# cp300_frehd.net
KiCad netlist of a schematic drawn in EAGLE
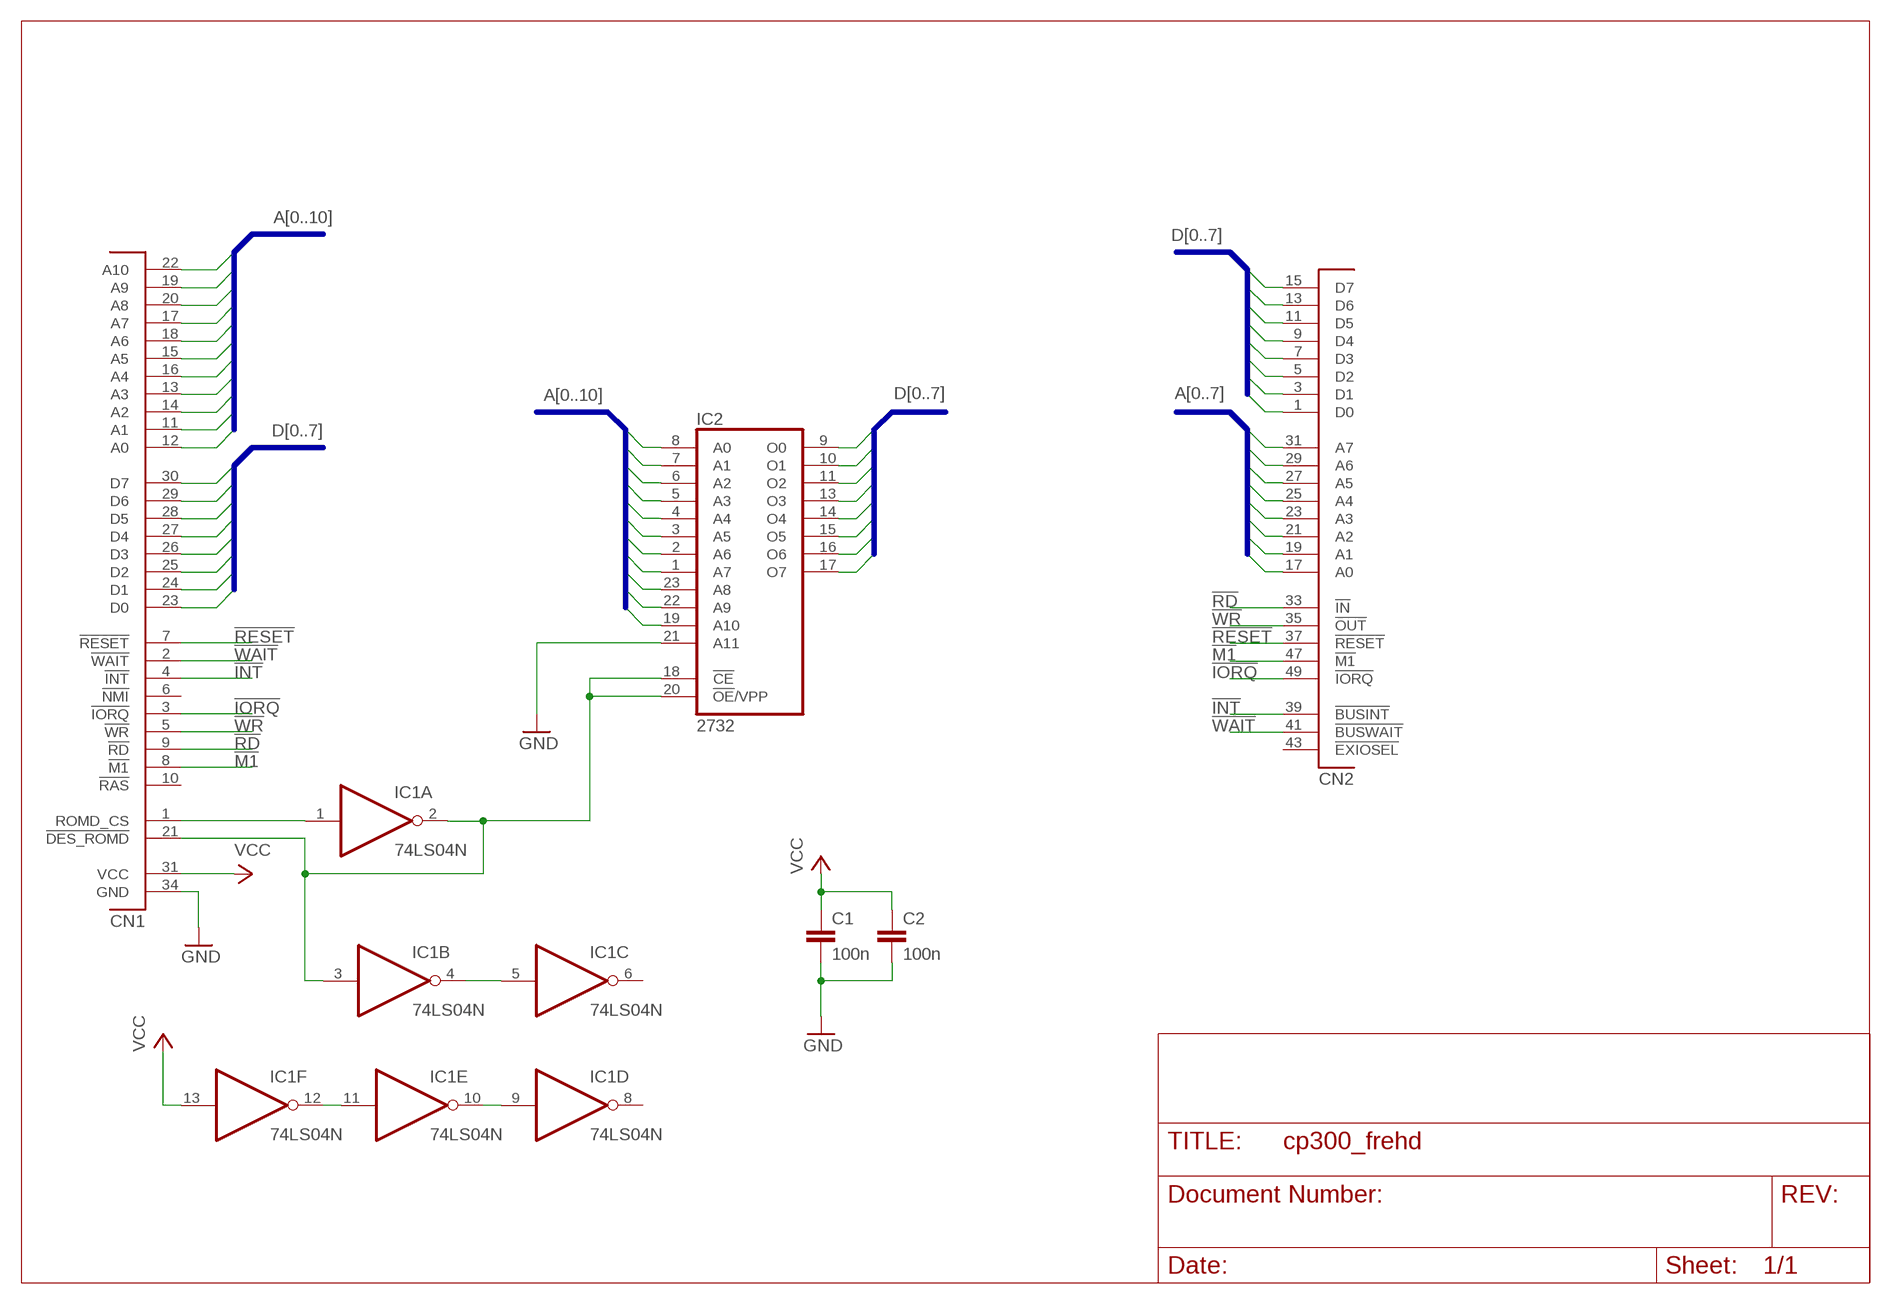
[diagram p0: schematic, sheet 1]

(export (version "E")
  (design (tool "Eeschema 10.0.6"))
  (components
    (comp (ref "C1")
      (value "100n")
      (footprint "eagle-import:C050-024X044")
      (libsource (lib "eagle-import") (part "C-EU050-024X044"))
    )
    (comp (ref "C2")
      (value "100n")
      (footprint "eagle-import:C050-024X044")
      (libsource (lib "eagle-import") (part "C-EU050-024X044"))
    )
    (comp (ref "CN1")
      (value "CP300_EXPA")
      (footprint "eagle-import:2X17")
      (libsource (lib "eagle-import") (part "CP300_EXPA"))
    )
    (comp (ref "CN2")
      (value "TRS80_EXPA")
      (footprint "eagle-import:2X25")
      (libsource (lib "eagle-import") (part "TRS80_EXPA"))
    )
    (comp (ref "IC1")
      (value "74LS04N")
      (footprint "eagle-import:DIL14")
      (libsource (lib "eagle-import") (part "7404NLS"))
    )
    (comp (ref "IC2")
      (value "2732")
      (footprint "eagle-import:DIL24")
      (libsource (lib "eagle-import") (part "2732"))
    )
  )
  (nets
    (net (code "1") (name "/A0") (class "Default")
      (node (ref "CN1") (pin "12") (pinfunction "A0_12") (pintype "output"))
      (node (ref "CN2") (pin "17") (pinfunction "A0_17") (pintype "output"))
      (node (ref "IC2") (pin "8") (pinfunction "A0_8") (pintype "input"))
    )
    (net (code "2") (name "/A1") (class "Default")
      (node (ref "CN1") (pin "11") (pinfunction "A1_11") (pintype "output"))
      (node (ref "CN2") (pin "19") (pinfunction "A1_19") (pintype "output"))
      (node (ref "IC2") (pin "7") (pinfunction "A1_7") (pintype "input"))
    )
    (net (code "3") (name "/A2") (class "Default")
      (node (ref "CN1") (pin "14") (pinfunction "A2_14") (pintype "output"))
      (node (ref "CN2") (pin "21") (pinfunction "A2_21") (pintype "output"))
      (node (ref "IC2") (pin "6") (pinfunction "A2_6") (pintype "input"))
    )
    (net (code "4") (name "/A3") (class "Default")
      (node (ref "CN1") (pin "13") (pinfunction "A3_13") (pintype "output"))
      (node (ref "CN2") (pin "23") (pinfunction "A3_23") (pintype "output"))
      (node (ref "IC2") (pin "5") (pinfunction "A3_5") (pintype "input"))
    )
    (net (code "5") (name "/A4") (class "Default")
      (node (ref "CN1") (pin "16") (pinfunction "A4_16") (pintype "output"))
      (node (ref "CN2") (pin "25") (pinfunction "A4_25") (pintype "output"))
      (node (ref "IC2") (pin "4") (pinfunction "A4_4") (pintype "input"))
    )
    (net (code "6") (name "/A5") (class "Default")
      (node (ref "CN1") (pin "15") (pinfunction "A5_15") (pintype "output"))
      (node (ref "CN2") (pin "27") (pinfunction "A5_27") (pintype "output"))
      (node (ref "CN2") (pin "29") (pinfunction "A6_29") (pintype "output"))
      (node (ref "IC2") (pin "3") (pinfunction "A5_3") (pintype "input"))
    )
    (net (code "7") (name "/A6") (class "Default")
      (node (ref "CN1") (pin "18") (pinfunction "A6_18") (pintype "output"))
      (node (ref "IC2") (pin "2") (pinfunction "A6_2") (pintype "input"))
    )
    (net (code "8") (name "/A7") (class "Default")
      (node (ref "CN1") (pin "17") (pinfunction "A7_17") (pintype "output"))
      (node (ref "CN2") (pin "31") (pinfunction "A7_31") (pintype "output"))
      (node (ref "IC2") (pin "1") (pinfunction "A7_1") (pintype "input"))
    )
    (net (code "9") (name "/A8") (class "Default")
      (node (ref "CN1") (pin "20") (pinfunction "A8_20") (pintype "output"))
      (node (ref "IC2") (pin "23") (pinfunction "A8_23") (pintype "input"))
    )
    (net (code "10") (name "/A9") (class "Default")
      (node (ref "CN1") (pin "19") (pinfunction "A9_19") (pintype "output"))
      (node (ref "IC2") (pin "22") (pinfunction "A9_22") (pintype "input"))
    )
    (net (code "11") (name "/A10") (class "Default")
      (node (ref "CN1") (pin "22") (pinfunction "A10_22") (pintype "output"))
      (node (ref "IC2") (pin "19") (pinfunction "A10_19") (pintype "input"))
    )
    (net (code "14") (name "/D0") (class "Default")
      (node (ref "CN1") (pin "23") (pinfunction "D0_23") (pintype "bidirectional"))
      (node (ref "CN2") (pin "1") (pinfunction "D0_1") (pintype "bidirectional"))
      (node (ref "IC2") (pin "9") (pinfunction "O0_9") (pintype "tri_state"))
    )
    (net (code "15") (name "/D1") (class "Default")
      (node (ref "CN1") (pin "24") (pinfunction "D1_24") (pintype "bidirectional"))
      (node (ref "CN2") (pin "3") (pinfunction "D1_3") (pintype "bidirectional"))
      (node (ref "IC2") (pin "10") (pinfunction "O1_10") (pintype "tri_state"))
    )
    (net (code "16") (name "/D2") (class "Default")
      (node (ref "CN1") (pin "25") (pinfunction "D2_25") (pintype "bidirectional"))
      (node (ref "CN2") (pin "5") (pinfunction "D2_5") (pintype "bidirectional"))
      (node (ref "IC2") (pin "11") (pinfunction "O2_11") (pintype "tri_state"))
    )
    (net (code "17") (name "/D3") (class "Default")
      (node (ref "CN1") (pin "26") (pinfunction "D3_26") (pintype "bidirectional"))
      (node (ref "CN2") (pin "7") (pinfunction "D3_7") (pintype "bidirectional"))
      (node (ref "IC2") (pin "13") (pinfunction "O3_13") (pintype "tri_state"))
    )
    (net (code "18") (name "/D4") (class "Default")
      (node (ref "CN1") (pin "27") (pinfunction "D4_27") (pintype "bidirectional"))
      (node (ref "CN2") (pin "9") (pinfunction "D4_9") (pintype "bidirectional"))
      (node (ref "IC2") (pin "14") (pinfunction "O4_14") (pintype "tri_state"))
    )
    (net (code "19") (name "/D5") (class "Default")
      (node (ref "CN1") (pin "28") (pinfunction "D5_28") (pintype "bidirectional"))
      (node (ref "CN2") (pin "11") (pinfunction "D5_11") (pintype "bidirectional"))
      (node (ref "IC2") (pin "15") (pinfunction "O5_15") (pintype "tri_state"))
    )
    (net (code "20") (name "/D6") (class "Default")
      (node (ref "CN1") (pin "29") (pinfunction "D6_29") (pintype "bidirectional"))
      (node (ref "CN2") (pin "13") (pinfunction "D6_13") (pintype "bidirectional"))
      (node (ref "IC2") (pin "16") (pinfunction "O6_16") (pintype "tri_state"))
    )
    (net (code "21") (name "/D7") (class "Default")
      (node (ref "CN1") (pin "30") (pinfunction "D7_30") (pintype "bidirectional"))
      (node (ref "CN2") (pin "15") (pinfunction "D7_15") (pintype "bidirectional"))
      (node (ref "IC2") (pin "17") (pinfunction "O7_17") (pintype "tri_state"))
    )
    (net (code "23") (name "/~{INT}") (class "Default")
      (node (ref "CN1") (pin "4") (pinfunction "~{INT}_4") (pintype "input"))
      (node (ref "CN2") (pin "39") (pinfunction "~{BUSINT}_39") (pintype "input"))
    )
    (net (code "24") (name "/~{IORQ}") (class "Default")
      (node (ref "CN1") (pin "3") (pinfunction "~{IORQ}_3") (pintype "output"))
      (node (ref "CN2") (pin "49") (pinfunction "~{IORQ}_49") (pintype "output"))
    )
    (net (code "25") (name "/~{M1}") (class "Default")
      (node (ref "CN1") (pin "8") (pinfunction "~{M1}_8") (pintype "output"))
      (node (ref "CN2") (pin "47") (pinfunction "~{M1}_47") (pintype "output"))
    )
    (net (code "26") (name "/~{RD}") (class "Default")
      (node (ref "CN1") (pin "9") (pinfunction "~{RD}_9") (pintype "output"))
      (node (ref "CN2") (pin "33") (pinfunction "~{IN}_33") (pintype "output"))
    )
    (net (code "27") (name "/~{RESET}") (class "Default")
      (node (ref "CN1") (pin "7") (pinfunction "~{RESET}_7") (pintype "output"))
      (node (ref "CN2") (pin "37") (pinfunction "~{RESET}_37") (pintype "output"))
    )
    (net (code "28") (name "/~{WAIT}") (class "Default")
      (node (ref "CN1") (pin "2") (pinfunction "~{WAIT}_2") (pintype "input"))
      (node (ref "CN2") (pin "41") (pinfunction "~{BUSWAIT}_41") (pintype "input"))
    )
    (net (code "29") (name "/~{WR}") (class "Default")
      (node (ref "CN1") (pin "5") (pinfunction "~{WR}_5") (pintype "output"))
      (node (ref "CN2") (pin "35") (pinfunction "~{OUT}_35") (pintype "output"))
    )
    (net (code "30") (name "GND") (class "Default")
      (node (ref "C1") (pin "2") (pinfunction "2_2") (pintype "passive"))
      (node (ref "C2") (pin "2") (pinfunction "2_2") (pintype "passive"))
      (node (ref "CN1") (pin "34") (pinfunction "GND_34") (pintype "power_in"))
      (node (ref "IC2") (pin "21") (pinfunction "A11_21") (pintype "input"))
    )
    (net (code "31") (name "Net-(CN1-ROMD_CS)") (class "Default")
      (node (ref "CN1") (pin "1") (pinfunction "ROMD_CS_1") (pintype "output"))
      (node (ref "IC1") (pin "1") (pinfunction "I_1") (pintype "input"))
    )
    (net (code "32") (name "Net-(CN1-~{DES_ROMD})") (class "Default")
      (node (ref "CN1") (pin "21") (pinfunction "~{DES_ROMD}_21") (pintype "input"))
      (node (ref "IC1") (pin "2") (pinfunction "O_2") (pintype "output"))
      (node (ref "IC1") (pin "3") (pinfunction "I_3") (pintype "input"))
      (node (ref "IC2") (pin "18") (pinfunction "~{CE}_18") (pintype "input"))
      (node (ref "IC2") (pin "20") (pinfunction "~{OE}/VPP_20") (pintype "input"))
    )
    (net (code "33") (name "Net-(IC1B-O)") (class "Default")
      (node (ref "IC1") (pin "4") (pinfunction "O_4") (pintype "output"))
      (node (ref "IC1") (pin "5") (pinfunction "I_5") (pintype "input"))
    )
    (net (code "34") (name "Net-(IC1D-I)") (class "Default")
      (node (ref "IC1") (pin "10") (pinfunction "O_10") (pintype "output"))
      (node (ref "IC1") (pin "9") (pinfunction "I_9") (pintype "input"))
    )
    (net (code "35") (name "Net-(IC1E-I)") (class "Default")
      (node (ref "IC1") (pin "11") (pinfunction "I_11") (pintype "input"))
      (node (ref "IC1") (pin "12") (pinfunction "O_12") (pintype "output"))
    )
    (net (code "36") (name "VCC") (class "Default")
      (node (ref "C1") (pin "1") (pinfunction "1_1") (pintype "passive"))
      (node (ref "C2") (pin "1") (pinfunction "1_1") (pintype "passive"))
      (node (ref "CN1") (pin "31") (pinfunction "VCC_31") (pintype "power_in"))
      (node (ref "IC1") (pin "13") (pinfunction "I_13") (pintype "input"))
    )
    (net (code "37") (name "unconnected-(CN1-~{NMI}-Pad6)") (class "Default")
      (node (ref "CN1") (pin "6") (pinfunction "~{NMI}_6") (pintype "input"))
    )
    (net (code "38") (name "unconnected-(CN1-~{RAS}-Pad10)") (class "Default")
      (node (ref "CN1") (pin "10") (pinfunction "~{RAS}_10") (pintype "output"))
    )
    (net (code "39") (name "unconnected-(CN2A-~{EXIOSEL}-Pad43)") (class "Default")
      (node (ref "CN2") (pin "43") (pinfunction "~{EXIOSEL}_43") (pintype "input"))
    )
    (net (code "40") (name "unconnected-(IC1C-O-Pad6)") (class "Default")
      (node (ref "IC1") (pin "6") (pinfunction "O_6") (pintype "output"))
    )
    (net (code "41") (name "unconnected-(IC1D-O-Pad8)") (class "Default")
      (node (ref "IC1") (pin "8") (pinfunction "O_8") (pintype "output"))
    )
  )
)
